# board.net
KiCad netlist of a schematic drawn in EAGLE
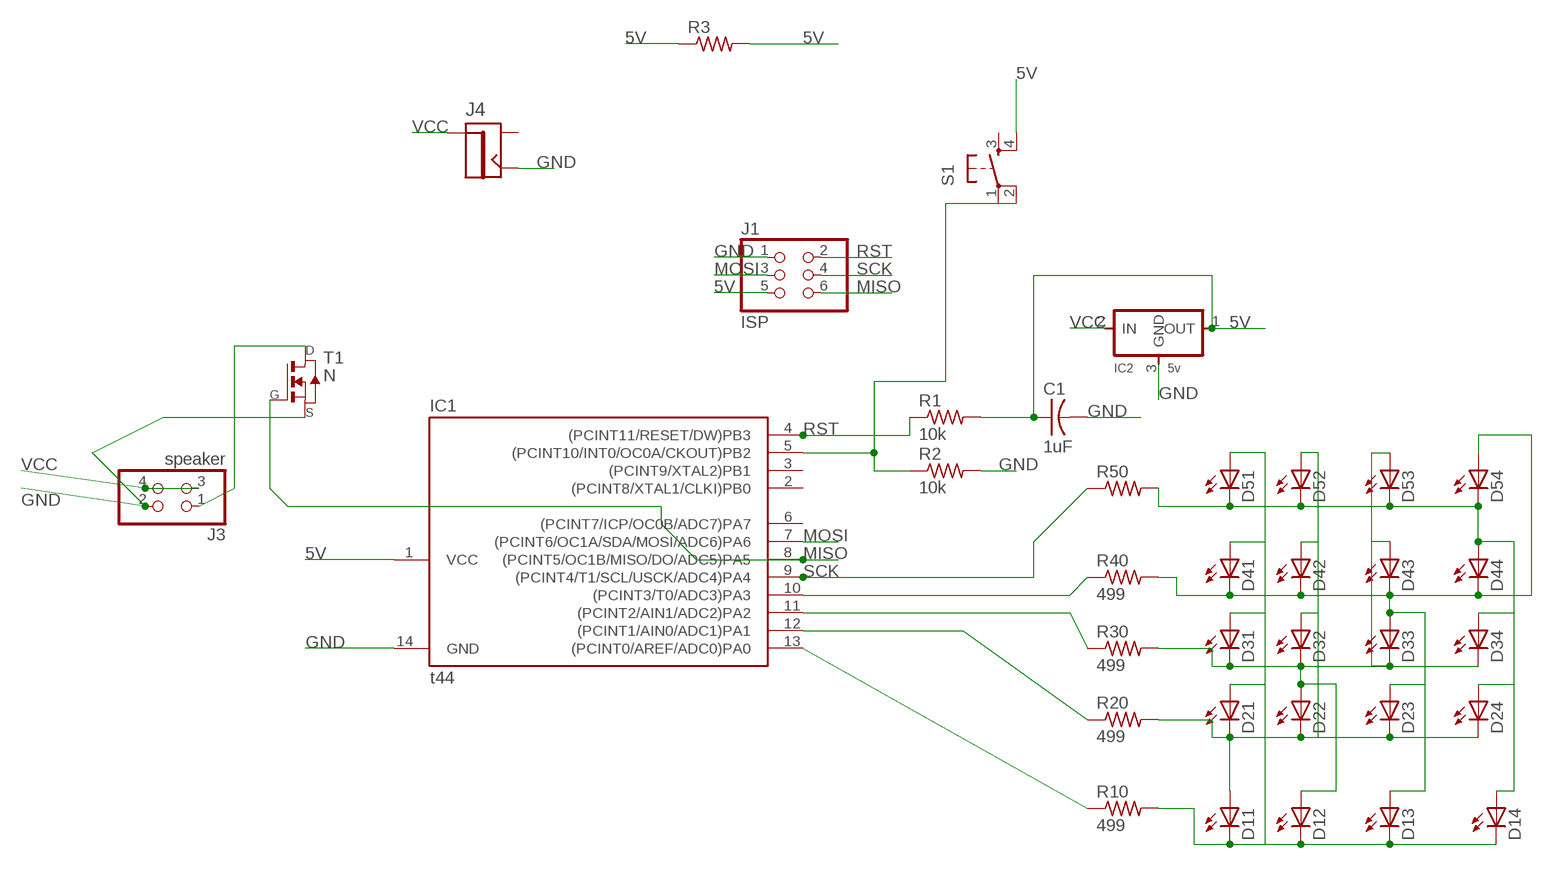
[diagram p0: schematic, sheet 1]

(export (version "E")
  (design (tool "Eeschema 10.0.6"))
  (components
    (comp (ref "C1")
      (value "1uF")
      (footprint "eagle-import:C1206FAB")
      (libsource (lib "eagle-import") (part "CAP-US1206FAB"))
    )
    (comp (ref "D11")
      (value "LEDFAB1206")
      (footprint "eagle-import:LED1206FAB")
      (libsource (lib "eagle-import") (part "LEDFAB1206"))
    )
    (comp (ref "D12")
      (value "LEDFAB1206")
      (footprint "eagle-import:LED1206FAB")
      (libsource (lib "eagle-import") (part "LEDFAB1206"))
    )
    (comp (ref "D13")
      (value "LEDFAB1206")
      (footprint "eagle-import:LED1206FAB")
      (libsource (lib "eagle-import") (part "LEDFAB1206"))
    )
    (comp (ref "D14")
      (value "LEDFAB1206")
      (footprint "eagle-import:LED1206FAB")
      (libsource (lib "eagle-import") (part "LEDFAB1206"))
    )
    (comp (ref "D21")
      (value "LEDFAB1206")
      (footprint "eagle-import:LED1206FAB")
      (libsource (lib "eagle-import") (part "LEDFAB1206"))
    )
    (comp (ref "D22")
      (value "LEDFAB1206")
      (footprint "eagle-import:LED1206FAB")
      (libsource (lib "eagle-import") (part "LEDFAB1206"))
    )
    (comp (ref "D23")
      (value "LEDFAB1206")
      (footprint "eagle-import:LED1206FAB")
      (libsource (lib "eagle-import") (part "LEDFAB1206"))
    )
    (comp (ref "D24")
      (value "LEDFAB1206")
      (footprint "eagle-import:LED1206FAB")
      (libsource (lib "eagle-import") (part "LEDFAB1206"))
    )
    (comp (ref "D31")
      (value "LEDFAB1206")
      (footprint "eagle-import:LED1206FAB")
      (libsource (lib "eagle-import") (part "LEDFAB1206"))
    )
    (comp (ref "D32")
      (value "LEDFAB1206")
      (footprint "eagle-import:LED1206FAB")
      (libsource (lib "eagle-import") (part "LEDFAB1206"))
    )
    (comp (ref "D33")
      (value "LEDFAB1206")
      (footprint "eagle-import:LED1206FAB")
      (libsource (lib "eagle-import") (part "LEDFAB1206"))
    )
    (comp (ref "D34")
      (value "LEDFAB1206")
      (footprint "eagle-import:LED1206FAB")
      (libsource (lib "eagle-import") (part "LEDFAB1206"))
    )
    (comp (ref "D41")
      (value "LEDFAB1206")
      (footprint "eagle-import:LED1206FAB")
      (libsource (lib "eagle-import") (part "LEDFAB1206"))
    )
    (comp (ref "D42")
      (value "LEDFAB1206")
      (footprint "eagle-import:LED1206FAB")
      (libsource (lib "eagle-import") (part "LEDFAB1206"))
    )
    (comp (ref "D43")
      (value "LEDFAB1206")
      (footprint "eagle-import:LED1206FAB")
      (libsource (lib "eagle-import") (part "LEDFAB1206"))
    )
    (comp (ref "D44")
      (value "LEDFAB1206")
      (footprint "eagle-import:LED1206FAB")
      (libsource (lib "eagle-import") (part "LEDFAB1206"))
    )
    (comp (ref "D51")
      (value "LEDFAB1206")
      (footprint "eagle-import:LED1206FAB")
      (libsource (lib "eagle-import") (part "LEDFAB1206"))
    )
    (comp (ref "D52")
      (value "LEDFAB1206")
      (footprint "eagle-import:LED1206FAB")
      (libsource (lib "eagle-import") (part "LEDFAB1206"))
    )
    (comp (ref "D53")
      (value "LEDFAB1206")
      (footprint "eagle-import:LED1206FAB")
      (libsource (lib "eagle-import") (part "LEDFAB1206"))
    )
    (comp (ref "D54")
      (value "LEDFAB1206")
      (footprint "eagle-import:LED1206FAB")
      (libsource (lib "eagle-import") (part "LEDFAB1206"))
    )
    (comp (ref "IC1")
      (value "t44")
      (footprint "eagle-import:SOIC14")
      (libsource (lib "eagle-import") (part "ATTINY44-SSU"))
    )
    (comp (ref "IC2")
      (value "5v")
      (footprint "eagle-import:SOT23")
      (libsource (lib "eagle-import") (part "REGULATORSOT23"))
    )
    (comp (ref "J1")
      (value "ISP")
      (footprint "eagle-import:2X03SMD")
      (libsource (lib "eagle-import") (part "PINHD-2X3-SMD"))
    )
    (comp (ref "J3")
      (value "speaker")
      (footprint "eagle-import:2X02SMD")
      (libsource (lib "eagle-import") (part "PINHD-2X2-SMD"))
    )
    (comp (ref "J4")
      (value "JACK2.1MM")
      (footprint "eagle-import:JACK_2.1MM")
      (libsource (lib "eagle-import") (part "JACK2.1MM"))
    )
    (comp (ref "R1")
      (value "10k")
      (footprint "eagle-import:R1206FAB")
      (libsource (lib "eagle-import") (part "RES-US1206FAB"))
    )
    (comp (ref "R2")
      (value "10k")
      (footprint "eagle-import:R1206FAB")
      (libsource (lib "eagle-import") (part "RES-US1206FAB"))
    )
    (comp (ref "R3")
      (value "RES-US1206FAB")
      (footprint "eagle-import:R1206FAB")
      (libsource (lib "eagle-import") (part "RES-US1206FAB"))
    )
    (comp (ref "R10")
      (value "499")
      (footprint "eagle-import:R1206FAB")
      (libsource (lib "eagle-import") (part "RES-US1206FAB"))
    )
    (comp (ref "R20")
      (value "499")
      (footprint "eagle-import:R1206FAB")
      (libsource (lib "eagle-import") (part "RES-US1206FAB"))
    )
    (comp (ref "R30")
      (value "499")
      (footprint "eagle-import:R1206FAB")
      (libsource (lib "eagle-import") (part "RES-US1206FAB"))
    )
    (comp (ref "R40")
      (value "499")
      (footprint "eagle-import:R1206FAB")
      (libsource (lib "eagle-import") (part "RES-US1206FAB"))
    )
    (comp (ref "R50")
      (value "RES-US1206FAB")
      (footprint "eagle-import:R1206FAB")
      (libsource (lib "eagle-import") (part "RES-US1206FAB"))
    )
    (comp (ref "S1")
      (value "6MM_SWITCH6MM_SWITCH")
      (footprint "eagle-import:6MM_SWITCH")
      (libsource (lib "eagle-import") (part "6MM_SWITCH6MM_SWITCH"))
    )
    (comp (ref "T1")
      (value "N")
      (footprint "eagle-import:SOT-23")
      (libsource (lib "eagle-import") (part "NMOSFETSOT23"))
    )
  )
  (nets
    (net (code "1") (name "/5V") (class "Default")
      (node (ref "C1") (pin "1") (pinfunction "1_1") (pintype "passive"))
      (node (ref "IC1") (pin "1") (pinfunction "VCC_1") (pintype "power_in"))
      (node (ref "IC2") (pin "1") (pinfunction "OUT_1") (pintype "bidirectional"))
      (node (ref "J1") (pin "5") (pinfunction "5_5") (pintype "passive"))
      (node (ref "R1") (pin "2") (pinfunction "2_2") (pintype "passive"))
      (node (ref "R3") (pin "1") (pinfunction "1_1") (pintype "passive"))
      (node (ref "R3") (pin "2") (pinfunction "2_2") (pintype "passive"))
      (node (ref "S1") (pin "4") (pinfunction "S1_4") (pintype "passive"))
    )
    (net (code "2") (name "/GND") (class "Default")
      (node (ref "C1") (pin "2") (pinfunction "2_2") (pintype "passive"))
      (node (ref "IC1") (pin "14") (pinfunction "GND_14") (pintype "power_in"))
      (node (ref "IC2") (pin "3") (pinfunction "GND_3") (pintype "bidirectional"))
      (node (ref "J1") (pin "1") (pinfunction "1_1") (pintype "passive"))
      (node (ref "J3") (pin "2") (pinfunction "2_2") (pintype "passive"))
      (node (ref "J4") (pin "CONTACT") (pinfunction "CONTACT_CONTACT") (pintype "bidirectional"))
      (node (ref "R2") (pin "2") (pinfunction "2_2") (pintype "passive"))
      (node (ref "T1") (pin "2") (pinfunction "S_2") (pintype "passive"))
    )
    (net (code "3") (name "/MISO") (class "Default")
      (node (ref "IC1") (pin "8") (pinfunction "(PCINT5/OC1B/MISO/DO/ADC5)PA5_8") (pintype "bidirectional"))
      (node (ref "J1") (pin "6") (pinfunction "6_6") (pintype "passive"))
      (node (ref "T1") (pin "3") (pinfunction "G_3") (pintype "passive"))
    )
    (net (code "4") (name "/MOSI") (class "Default")
      (node (ref "IC1") (pin "7") (pinfunction "(PCINT6/OC1A/SDA/MOSI/ADC6)PA6_7") (pintype "bidirectional"))
      (node (ref "J1") (pin "3") (pinfunction "3_3") (pintype "passive"))
    )
    (net (code "5") (name "/RST") (class "Default")
      (node (ref "IC1") (pin "4") (pinfunction "(PCINT11/RESET/DW)PB3_4") (pintype "bidirectional"))
      (node (ref "J1") (pin "2") (pinfunction "2_2") (pintype "passive"))
      (node (ref "R1") (pin "1") (pinfunction "1_1") (pintype "passive"))
    )
    (net (code "6") (name "/SCK") (class "Default")
      (node (ref "IC1") (pin "9") (pinfunction "(PCINT4/T1/SCL/USCK/ADC4)PA4_9") (pintype "bidirectional"))
      (node (ref "J1") (pin "4") (pinfunction "4_4") (pintype "passive"))
      (node (ref "R50") (pin "1") (pinfunction "1_1") (pintype "passive"))
    )
    (net (code "7") (name "/VCC") (class "Default")
      (node (ref "IC2") (pin "2") (pinfunction "IN_2") (pintype "bidirectional"))
      (node (ref "J3") (pin "3") (pinfunction "3_3") (pintype "passive"))
      (node (ref "J3") (pin "4") (pinfunction "4_4") (pintype "passive"))
      (node (ref "J4") (pin "PIN") (pinfunction "PIN_PIN") (pintype "bidirectional"))
    )
    (net (code "8") (name "Net-(D11-A)") (class "Default")
      (node (ref "D11") (pin "1") (pinfunction "A_1") (pintype "passive"))
      (node (ref "D21") (pin "2") (pinfunction "C_2") (pintype "passive"))
      (node (ref "D22") (pin "2") (pinfunction "C_2") (pintype "passive"))
      (node (ref "D23") (pin "2") (pinfunction "C_2") (pintype "passive"))
      (node (ref "D24") (pin "2") (pinfunction "C_2") (pintype "passive"))
      (node (ref "D32") (pin "1") (pinfunction "A_1") (pintype "passive"))
      (node (ref "D42") (pin "1") (pinfunction "A_1") (pintype "passive"))
      (node (ref "D52") (pin "1") (pinfunction "A_1") (pintype "passive"))
      (node (ref "R20") (pin "2") (pinfunction "2_2") (pintype "passive"))
    )
    (net (code "9") (name "Net-(D11-C)") (class "Default")
      (node (ref "D11") (pin "2") (pinfunction "C_2") (pintype "passive"))
      (node (ref "D12") (pin "2") (pinfunction "C_2") (pintype "passive"))
      (node (ref "D13") (pin "2") (pinfunction "C_2") (pintype "passive"))
      (node (ref "D14") (pin "2") (pinfunction "C_2") (pintype "passive"))
      (node (ref "D21") (pin "1") (pinfunction "A_1") (pintype "passive"))
      (node (ref "D31") (pin "1") (pinfunction "A_1") (pintype "passive"))
      (node (ref "D41") (pin "1") (pinfunction "A_1") (pintype "passive"))
      (node (ref "D51") (pin "1") (pinfunction "A_1") (pintype "passive"))
      (node (ref "R10") (pin "2") (pinfunction "2_2") (pintype "passive"))
    )
    (net (code "10") (name "Net-(D12-A)") (class "Default")
      (node (ref "D12") (pin "1") (pinfunction "A_1") (pintype "passive"))
      (node (ref "D22") (pin "1") (pinfunction "A_1") (pintype "passive"))
      (node (ref "D31") (pin "2") (pinfunction "C_2") (pintype "passive"))
      (node (ref "D32") (pin "2") (pinfunction "C_2") (pintype "passive"))
      (node (ref "D33") (pin "2") (pinfunction "C_2") (pintype "passive"))
      (node (ref "D34") (pin "2") (pinfunction "C_2") (pintype "passive"))
      (node (ref "D43") (pin "1") (pinfunction "A_1") (pintype "passive"))
      (node (ref "D53") (pin "1") (pinfunction "A_1") (pintype "passive"))
      (node (ref "R30") (pin "2") (pinfunction "2_2") (pintype "passive"))
    )
    (net (code "11") (name "Net-(D13-A)") (class "Default")
      (node (ref "D13") (pin "1") (pinfunction "A_1") (pintype "passive"))
      (node (ref "D23") (pin "1") (pinfunction "A_1") (pintype "passive"))
      (node (ref "D33") (pin "1") (pinfunction "A_1") (pintype "passive"))
      (node (ref "D41") (pin "2") (pinfunction "C_2") (pintype "passive"))
      (node (ref "D42") (pin "2") (pinfunction "C_2") (pintype "passive"))
      (node (ref "D43") (pin "2") (pinfunction "C_2") (pintype "passive"))
      (node (ref "D44") (pin "2") (pinfunction "C_2") (pintype "passive"))
      (node (ref "D54") (pin "1") (pinfunction "A_1") (pintype "passive"))
      (node (ref "R40") (pin "2") (pinfunction "2_2") (pintype "passive"))
    )
    (net (code "12") (name "Net-(D14-A)") (class "Default")
      (node (ref "D14") (pin "1") (pinfunction "A_1") (pintype "passive"))
      (node (ref "D24") (pin "1") (pinfunction "A_1") (pintype "passive"))
      (node (ref "D34") (pin "1") (pinfunction "A_1") (pintype "passive"))
      (node (ref "D44") (pin "1") (pinfunction "A_1") (pintype "passive"))
      (node (ref "D51") (pin "2") (pinfunction "C_2") (pintype "passive"))
      (node (ref "D52") (pin "2") (pinfunction "C_2") (pintype "passive"))
      (node (ref "D53") (pin "2") (pinfunction "C_2") (pintype "passive"))
      (node (ref "D54") (pin "2") (pinfunction "C_2") (pintype "passive"))
      (node (ref "R50") (pin "2") (pinfunction "2_2") (pintype "passive"))
    )
    (net (code "13") (name "Net-(IC1-(PCINT0{slash}AREF{slash}ADC0)PA0)") (class "Default")
      (node (ref "IC1") (pin "13") (pinfunction "(PCINT0/AREF/ADC0)PA0_13") (pintype "bidirectional"))
      (node (ref "R10") (pin "1") (pinfunction "1_1") (pintype "passive"))
    )
    (net (code "14") (name "Net-(IC1-(PCINT1{slash}AIN0{slash}ADC1)PA1)") (class "Default")
      (node (ref "IC1") (pin "12") (pinfunction "(PCINT1/AIN0/ADC1)PA1_12") (pintype "bidirectional"))
      (node (ref "R20") (pin "1") (pinfunction "1_1") (pintype "passive"))
    )
    (net (code "15") (name "Net-(IC1-(PCINT2{slash}AIN1{slash}ADC2)PA2)") (class "Default")
      (node (ref "IC1") (pin "11") (pinfunction "(PCINT2/AIN1/ADC2)PA2_11") (pintype "bidirectional"))
      (node (ref "R30") (pin "1") (pinfunction "1_1") (pintype "passive"))
    )
    (net (code "16") (name "Net-(IC1-(PCINT3{slash}T0{slash}ADC3)PA3)") (class "Default")
      (node (ref "IC1") (pin "10") (pinfunction "(PCINT3/T0/ADC3)PA3_10") (pintype "bidirectional"))
      (node (ref "R40") (pin "1") (pinfunction "1_1") (pintype "passive"))
    )
    (net (code "17") (name "Net-(IC1-(PCINT10{slash}INT0{slash}OC0A{slash}CKOUT)PB2)") (class "Default")
      (node (ref "IC1") (pin "5") (pinfunction "(PCINT10/INT0/OC0A/CKOUT)PB2_5") (pintype "bidirectional"))
      (node (ref "R2") (pin "1") (pinfunction "1_1") (pintype "passive"))
      (node (ref "S1") (pin "2") (pinfunction "P1_2") (pintype "passive"))
    )
    (net (code "18") (name "Net-(T1-D)") (class "Default")
      (node (ref "J3") (pin "1") (pinfunction "1_1") (pintype "passive"))
      (node (ref "T1") (pin "1") (pinfunction "D_1") (pintype "passive"))
    )
    (net (code "19") (name "unconnected-(IC1-(PCINT7{slash}ICP{slash}OC0B{slash}ADC7)PA7-Pad6)") (class "Default")
      (node (ref "IC1") (pin "6") (pinfunction "(PCINT7/ICP/OC0B/ADC7)PA7_6") (pintype "bidirectional"))
    )
    (net (code "20") (name "unconnected-(IC1-(PCINT8{slash}XTAL1{slash}CLKI)PB0-Pad2)") (class "Default")
      (node (ref "IC1") (pin "2") (pinfunction "(PCINT8/XTAL1/CLKI)PB0_2") (pintype "bidirectional"))
    )
    (net (code "21") (name "unconnected-(IC1-(PCINT9{slash}XTAL2)PB1-Pad3)") (class "Default")
      (node (ref "IC1") (pin "3") (pinfunction "(PCINT9/XTAL2)PB1_3") (pintype "bidirectional"))
    )
    (net (code "22") (name "unconnected-(J4-PadSHUNT)") (class "Default")
      (node (ref "J4") (pin "SHUNT") (pinfunction "SHUNT_SHUNT") (pintype "bidirectional"))
    )
    (net (code "23") (name "unconnected-(S1-P-Pad1)") (class "Default")
      (node (ref "S1") (pin "1") (pinfunction "P_1") (pintype "passive"))
    )
    (net (code "24") (name "unconnected-(S1-S-Pad3)") (class "Default")
      (node (ref "S1") (pin "3") (pinfunction "S_3") (pintype "passive"))
    )
  )
)
